# peripherals-headers.net
KiCad netlist of a schematic drawn in Altium Designer
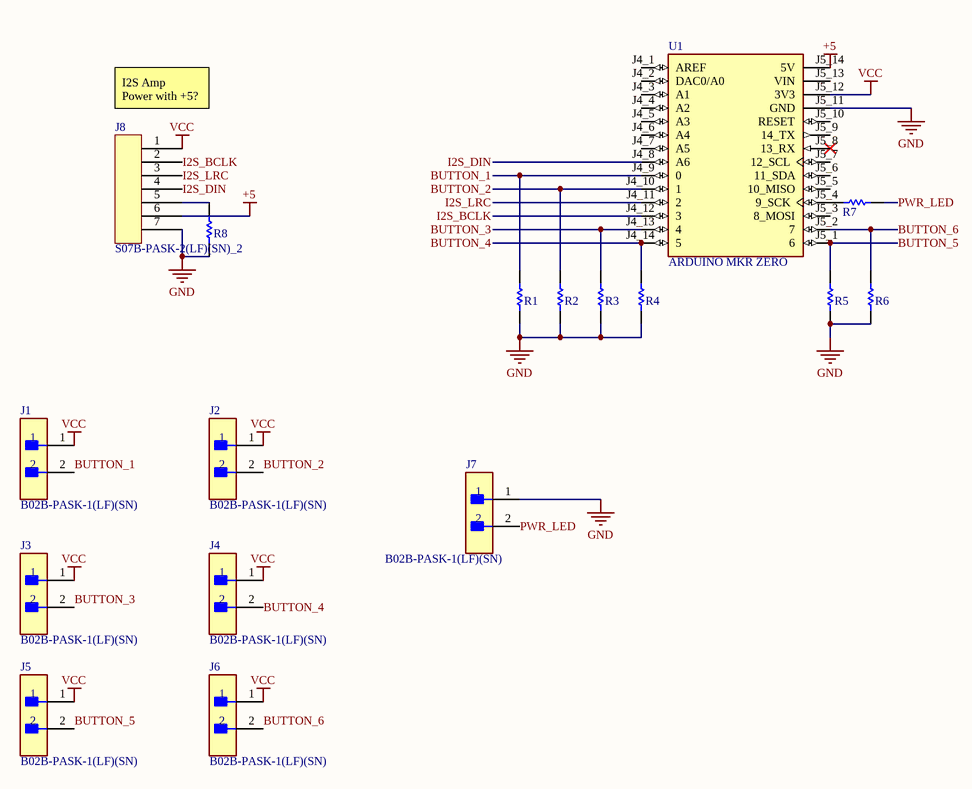
[diagram p0: peripherals-headers.SchDoc]

(export (version "E")
  (design (tool "Eeschema 10.0.6"))
  (components
    (comp (ref "J1")
      (value "B02B-PASK-1(LF)(SN)")
      (footprint "FP-B02B-PASK-1_LF_SN-MFG")
      (description "CONN HEADER VERT 2POS 2MM")
      (libsource (lib "Altium Content Vault") (part "3bc925449376181038e59eaffc5286c"))
    )
    (comp (ref "J2")
      (value "B02B-PASK-1(LF)(SN)")
      (footprint "FP-B02B-PASK-1_LF_SN-MFG")
      (description "CONN HEADER VERT 2POS 2MM")
      (libsource (lib "Altium Content Vault") (part "3bc925449376181038e59eaffc5286c"))
    )
    (comp (ref "J3")
      (value "B02B-PASK-1(LF)(SN)")
      (footprint "FP-B02B-PASK-1_LF_SN-MFG")
      (description "CONN HEADER VERT 2POS 2MM")
      (libsource (lib "Altium Content Vault") (part "3bc925449376181038e59eaffc5286c"))
    )
    (comp (ref "J4")
      (value "B02B-PASK-1(LF)(SN)")
      (footprint "FP-B02B-PASK-1_LF_SN-MFG")
      (description "CONN HEADER VERT 2POS 2MM")
      (libsource (lib "Altium Content Vault") (part "3bc925449376181038e59eaffc5286c"))
    )
    (comp (ref "J5")
      (value "B02B-PASK-1(LF)(SN)")
      (footprint "FP-B02B-PASK-1_LF_SN-MFG")
      (description "CONN HEADER VERT 2POS 2MM")
      (libsource (lib "Altium Content Vault") (part "3bc925449376181038e59eaffc5286c"))
    )
    (comp (ref "J6")
      (value "B02B-PASK-1(LF)(SN)")
      (footprint "FP-B02B-PASK-1_LF_SN-MFG")
      (description "CONN HEADER VERT 2POS 2MM")
      (libsource (lib "Altium Content Vault") (part "3bc925449376181038e59eaffc5286c"))
    )
    (comp (ref "J7")
      (value "B02B-PASK-1(LF)(SN)")
      (footprint "FP-B02B-PASK-1_LF_SN-MFG")
      (description "CONN HEADER VERT 2POS 2MM")
      (libsource (lib "Altium Content Vault") (part "3bc925449376181038e59eaffc5286c"))
    )
    (comp (ref "J8")
      (value "S07B-PASK-2(LF)(SN)_2")
      (footprint "S07B-PASK-2(LF)(SN)_2-Footprint-1")
      (description "Conn Shrouded Header HDR 7 POS 2mm Solder RA Thru-Hole Box")
      (libsource (lib "University of Pittsburgh") (part "S07B-PASK-2(LF)(SN)"))
    )
    (comp (ref "R1")
      (value "1k Through-Hole 1/4W")
      (footprint "RESA60-630X240")
      (description "RES 1K OHM 1/4W 1% AXIAL")
      (fields (field (name "TOLERANCE") "1%"))
      (libsource (lib "University of Pittsburgh") (part "RES-2"))
    )
    (comp (ref "R2")
      (value "1k Through-Hole 1/4W")
      (footprint "RESA60-630X240")
      (description "RES 1K OHM 1/4W 1% AXIAL")
      (fields (field (name "TOLERANCE") "1%"))
      (libsource (lib "University of Pittsburgh") (part "RES-2"))
    )
    (comp (ref "R3")
      (value "1k Through-Hole 1/4W")
      (footprint "RESA60-630X240")
      (description "RES 1K OHM 1/4W 1% AXIAL")
      (fields (field (name "TOLERANCE") "1%"))
      (libsource (lib "University of Pittsburgh") (part "RES-2"))
    )
    (comp (ref "R4")
      (value "1k Through-Hole 1/4W")
      (footprint "RESA60-630X240")
      (description "RES 1K OHM 1/4W 1% AXIAL")
      (fields (field (name "TOLERANCE") "1%"))
      (libsource (lib "University of Pittsburgh") (part "RES-2"))
    )
    (comp (ref "R5")
      (value "1k Through-Hole 1/4W")
      (footprint "RESA60-630X240")
      (description "RES 1K OHM 1/4W 1% AXIAL")
      (fields (field (name "TOLERANCE") "1%"))
      (libsource (lib "University of Pittsburgh") (part "RES-2"))
    )
    (comp (ref "R6")
      (value "1k Through-Hole 1/4W")
      (footprint "RESA60-630X240")
      (description "RES 1K OHM 1/4W 1% AXIAL")
      (fields (field (name "TOLERANCE") "1%"))
      (libsource (lib "University of Pittsburgh") (part "RES-2"))
    )
    (comp (ref "R7")
      (value "1k Through-Hole 1/4W")
      (footprint "RESA60-630X240")
      (description "RES 1K OHM 1/4W 1% AXIAL")
      (fields (field (name "TOLERANCE") "1%"))
      (libsource (lib "University of Pittsburgh") (part "RES-2"))
    )
    (comp (ref "R8")
      (value "1k Through-Hole 1/4W")
      (footprint "RESA60-630X240")
      (description "RES 1K OHM 1/4W 1% AXIAL")
      (fields (field (name "TOLERANCE") "1%"))
      (libsource (lib "University of Pittsburgh") (part "RES-2"))
    )
    (comp (ref "U1")
      (value "ARDUINO MKR ZERO")
      (footprint "ARDUINO MKR ZERO-Footprint-1")
      (description "SEN PHT LO/DO M8 4PIN NO BRKT")
      (libsource (lib "University of Pittsburgh") (part "ARDUINO MKR ZERO-Symbol-1"))
    )
  )
  (nets
    (net (code "1") (name "+5") (class "Default")
      (node (ref "J8") (pin "6") (pintype "passive"))
      (node (ref "U1") (pin "J5_14") (pinfunction "5V_J5_14") (pintype "power_in"))
    )
    (net (code "2") (name "/BUTTON_1") (class "Default")
      (node (ref "J1") (pin "2") (pinfunction "2_2") (pintype "passive"))
      (node (ref "R1") (pin "2") (pinfunction "2_2") (pintype "passive"))
      (node (ref "U1") (pin "J4_9") (pinfunction "0_J4_9") (pintype "bidirectional"))
    )
    (net (code "3") (name "/BUTTON_2") (class "Default")
      (node (ref "J2") (pin "2") (pinfunction "2_2") (pintype "passive"))
      (node (ref "R2") (pin "2") (pinfunction "2_2") (pintype "passive"))
      (node (ref "U1") (pin "J4_10") (pinfunction "1_J4_10") (pintype "bidirectional"))
    )
    (net (code "4") (name "/BUTTON_3") (class "Default")
      (node (ref "J3") (pin "2") (pinfunction "2_2") (pintype "passive"))
      (node (ref "R3") (pin "2") (pinfunction "2_2") (pintype "passive"))
      (node (ref "U1") (pin "J4_13") (pinfunction "4_J4_13") (pintype "bidirectional"))
    )
    (net (code "5") (name "/BUTTON_4") (class "Default")
      (node (ref "J4") (pin "2") (pinfunction "2_2") (pintype "passive"))
      (node (ref "R4") (pin "2") (pinfunction "2_2") (pintype "passive"))
      (node (ref "U1") (pin "J4_14") (pinfunction "5_J4_14") (pintype "bidirectional"))
    )
    (net (code "6") (name "/BUTTON_5") (class "Default")
      (node (ref "J5") (pin "2") (pinfunction "2_2") (pintype "passive"))
      (node (ref "R5") (pin "2") (pinfunction "2_2") (pintype "passive"))
      (node (ref "U1") (pin "J5_1") (pinfunction "6_J5_1") (pintype "bidirectional"))
    )
    (net (code "7") (name "/BUTTON_6") (class "Default")
      (node (ref "J6") (pin "2") (pinfunction "2_2") (pintype "passive"))
      (node (ref "R6") (pin "2") (pinfunction "2_2") (pintype "passive"))
      (node (ref "U1") (pin "J5_2") (pinfunction "7_J5_2") (pintype "bidirectional"))
    )
    (net (code "8") (name "/I2S_BCLK") (class "Default")
      (node (ref "J8") (pin "2") (pintype "passive"))
      (node (ref "U1") (pin "J4_12") (pinfunction "3_J4_12") (pintype "bidirectional"))
    )
    (net (code "9") (name "/I2S_DIN") (class "Default")
      (node (ref "J8") (pin "4") (pintype "passive"))
      (node (ref "U1") (pin "J4_8") (pinfunction "A6_J4_8") (pintype "bidirectional"))
    )
    (net (code "10") (name "/I2S_LRC") (class "Default")
      (node (ref "J8") (pin "3") (pintype "passive"))
      (node (ref "U1") (pin "J4_11") (pinfunction "2_J4_11") (pintype "bidirectional"))
    )
    (net (code "11") (name "/PWR_LED") (class "Default")
      (node (ref "J7") (pin "2") (pinfunction "2_2") (pintype "passive"))
      (node (ref "R7") (pin "1") (pinfunction "1_1") (pintype "passive"))
    )
    (net (code "12") (name "GND") (class "Default")
      (node (ref "J7") (pin "1") (pinfunction "1_1") (pintype "passive"))
      (node (ref "J8") (pin "7") (pintype "passive"))
      (node (ref "R1") (pin "1") (pinfunction "1_1") (pintype "passive"))
      (node (ref "R2") (pin "1") (pinfunction "1_1") (pintype "passive"))
      (node (ref "R3") (pin "1") (pinfunction "1_1") (pintype "passive"))
      (node (ref "R4") (pin "1") (pinfunction "1_1") (pintype "passive"))
      (node (ref "R5") (pin "1") (pinfunction "1_1") (pintype "passive"))
      (node (ref "R6") (pin "1") (pinfunction "1_1") (pintype "passive"))
      (node (ref "R8") (pin "1") (pinfunction "1_1") (pintype "passive"))
      (node (ref "U1") (pin "J5_11") (pinfunction "GND_J5_11") (pintype "power_in"))
    )
    (net (code "13") (name "Net-(J8-Pad5)") (class "Default")
      (node (ref "J8") (pin "5") (pintype "passive"))
      (node (ref "R8") (pin "2") (pinfunction "2_2") (pintype "passive"))
    )
    (net (code "14") (name "Net-(U1-9_SCK)") (class "Default")
      (node (ref "R7") (pin "2") (pinfunction "2_2") (pintype "passive"))
      (node (ref "U1") (pin "J5_4") (pinfunction "9_SCK_J5_4") (pintype "bidirectional"))
    )
    (net (code "15") (name "VCC") (class "Default")
      (node (ref "J1") (pin "1") (pinfunction "1_1") (pintype "passive"))
      (node (ref "J2") (pin "1") (pinfunction "1_1") (pintype "passive"))
      (node (ref "J3") (pin "1") (pinfunction "1_1") (pintype "passive"))
      (node (ref "J4") (pin "1") (pinfunction "1_1") (pintype "passive"))
      (node (ref "J5") (pin "1") (pinfunction "1_1") (pintype "passive"))
      (node (ref "J6") (pin "1") (pinfunction "1_1") (pintype "passive"))
      (node (ref "J8") (pin "1") (pintype "passive"))
      (node (ref "U1") (pin "J5_12") (pinfunction "3V3_J5_12") (pintype "power_in"))
    )
    (net (code "16") (name "unconnected-(U1-8_MOSI-PadJ5_3)") (class "Default")
      (node (ref "U1") (pin "J5_3") (pinfunction "8_MOSI_J5_3") (pintype "bidirectional"))
    )
    (net (code "17") (name "unconnected-(U1-10_MISO-PadJ5_5)") (class "Default")
      (node (ref "U1") (pin "J5_5") (pinfunction "10_MISO_J5_5") (pintype "bidirectional"))
    )
    (net (code "18") (name "unconnected-(U1-11_SDA-PadJ5_6)") (class "Default")
      (node (ref "U1") (pin "J5_6") (pinfunction "11_SDA_J5_6") (pintype "bidirectional"))
    )
    (net (code "19") (name "unconnected-(U1-12_SCL-PadJ5_7)") (class "Default")
      (node (ref "U1") (pin "J5_7") (pinfunction "12_SCL_J5_7") (pintype "bidirectional"))
    )
    (net (code "20") (name "unconnected-(U1-13_RX-PadJ5_8)") (class "Default")
      (node (ref "U1") (pin "J5_8") (pinfunction "13_RX_J5_8") (pintype "input+no_connect"))
    )
    (net (code "21") (name "unconnected-(U1-14_TX-PadJ5_9)") (class "Default")
      (node (ref "U1") (pin "J5_9") (pinfunction "14_TX_J5_9") (pintype "output"))
    )
    (net (code "22") (name "unconnected-(U1-A1-PadJ4_3)") (class "Default")
      (node (ref "U1") (pin "J4_3") (pinfunction "A1_J4_3") (pintype "bidirectional"))
    )
    (net (code "23") (name "unconnected-(U1-A2-PadJ4_4)") (class "Default")
      (node (ref "U1") (pin "J4_4") (pinfunction "A2_J4_4") (pintype "bidirectional"))
    )
    (net (code "24") (name "unconnected-(U1-A3-PadJ4_5)") (class "Default")
      (node (ref "U1") (pin "J4_5") (pinfunction "A3_J4_5") (pintype "bidirectional"))
    )
    (net (code "25") (name "unconnected-(U1-A4-PadJ4_6)") (class "Default")
      (node (ref "U1") (pin "J4_6") (pinfunction "A4_J4_6") (pintype "bidirectional"))
    )
    (net (code "26") (name "unconnected-(U1-A5-PadJ4_7)") (class "Default")
      (node (ref "U1") (pin "J4_7") (pinfunction "A5_J4_7") (pintype "bidirectional"))
    )
    (net (code "27") (name "unconnected-(U1-AREF-PadJ4_1)") (class "Default")
      (node (ref "U1") (pin "J4_1") (pinfunction "AREF_J4_1") (pintype "bidirectional"))
    )
    (net (code "28") (name "unconnected-(U1-DAC0{slash}A0-PadJ4_2)") (class "Default")
      (node (ref "U1") (pin "J4_2") (pinfunction "DAC0/A0_J4_2") (pintype "bidirectional"))
    )
    (net (code "29") (name "unconnected-(U1-RESET-PadJ5_10)") (class "Default")
      (node (ref "U1") (pin "J5_10") (pinfunction "RESET_J5_10") (pintype "bidirectional"))
    )
    (net (code "30") (name "unconnected-(U1-VIN-PadJ5_13)") (class "Default")
      (node (ref "U1") (pin "J5_13") (pinfunction "VIN_J5_13") (pintype "power_in"))
    )
  )
)
